# ovencontrol.net
KiCad netlist of a schematic drawn in Altium Designer
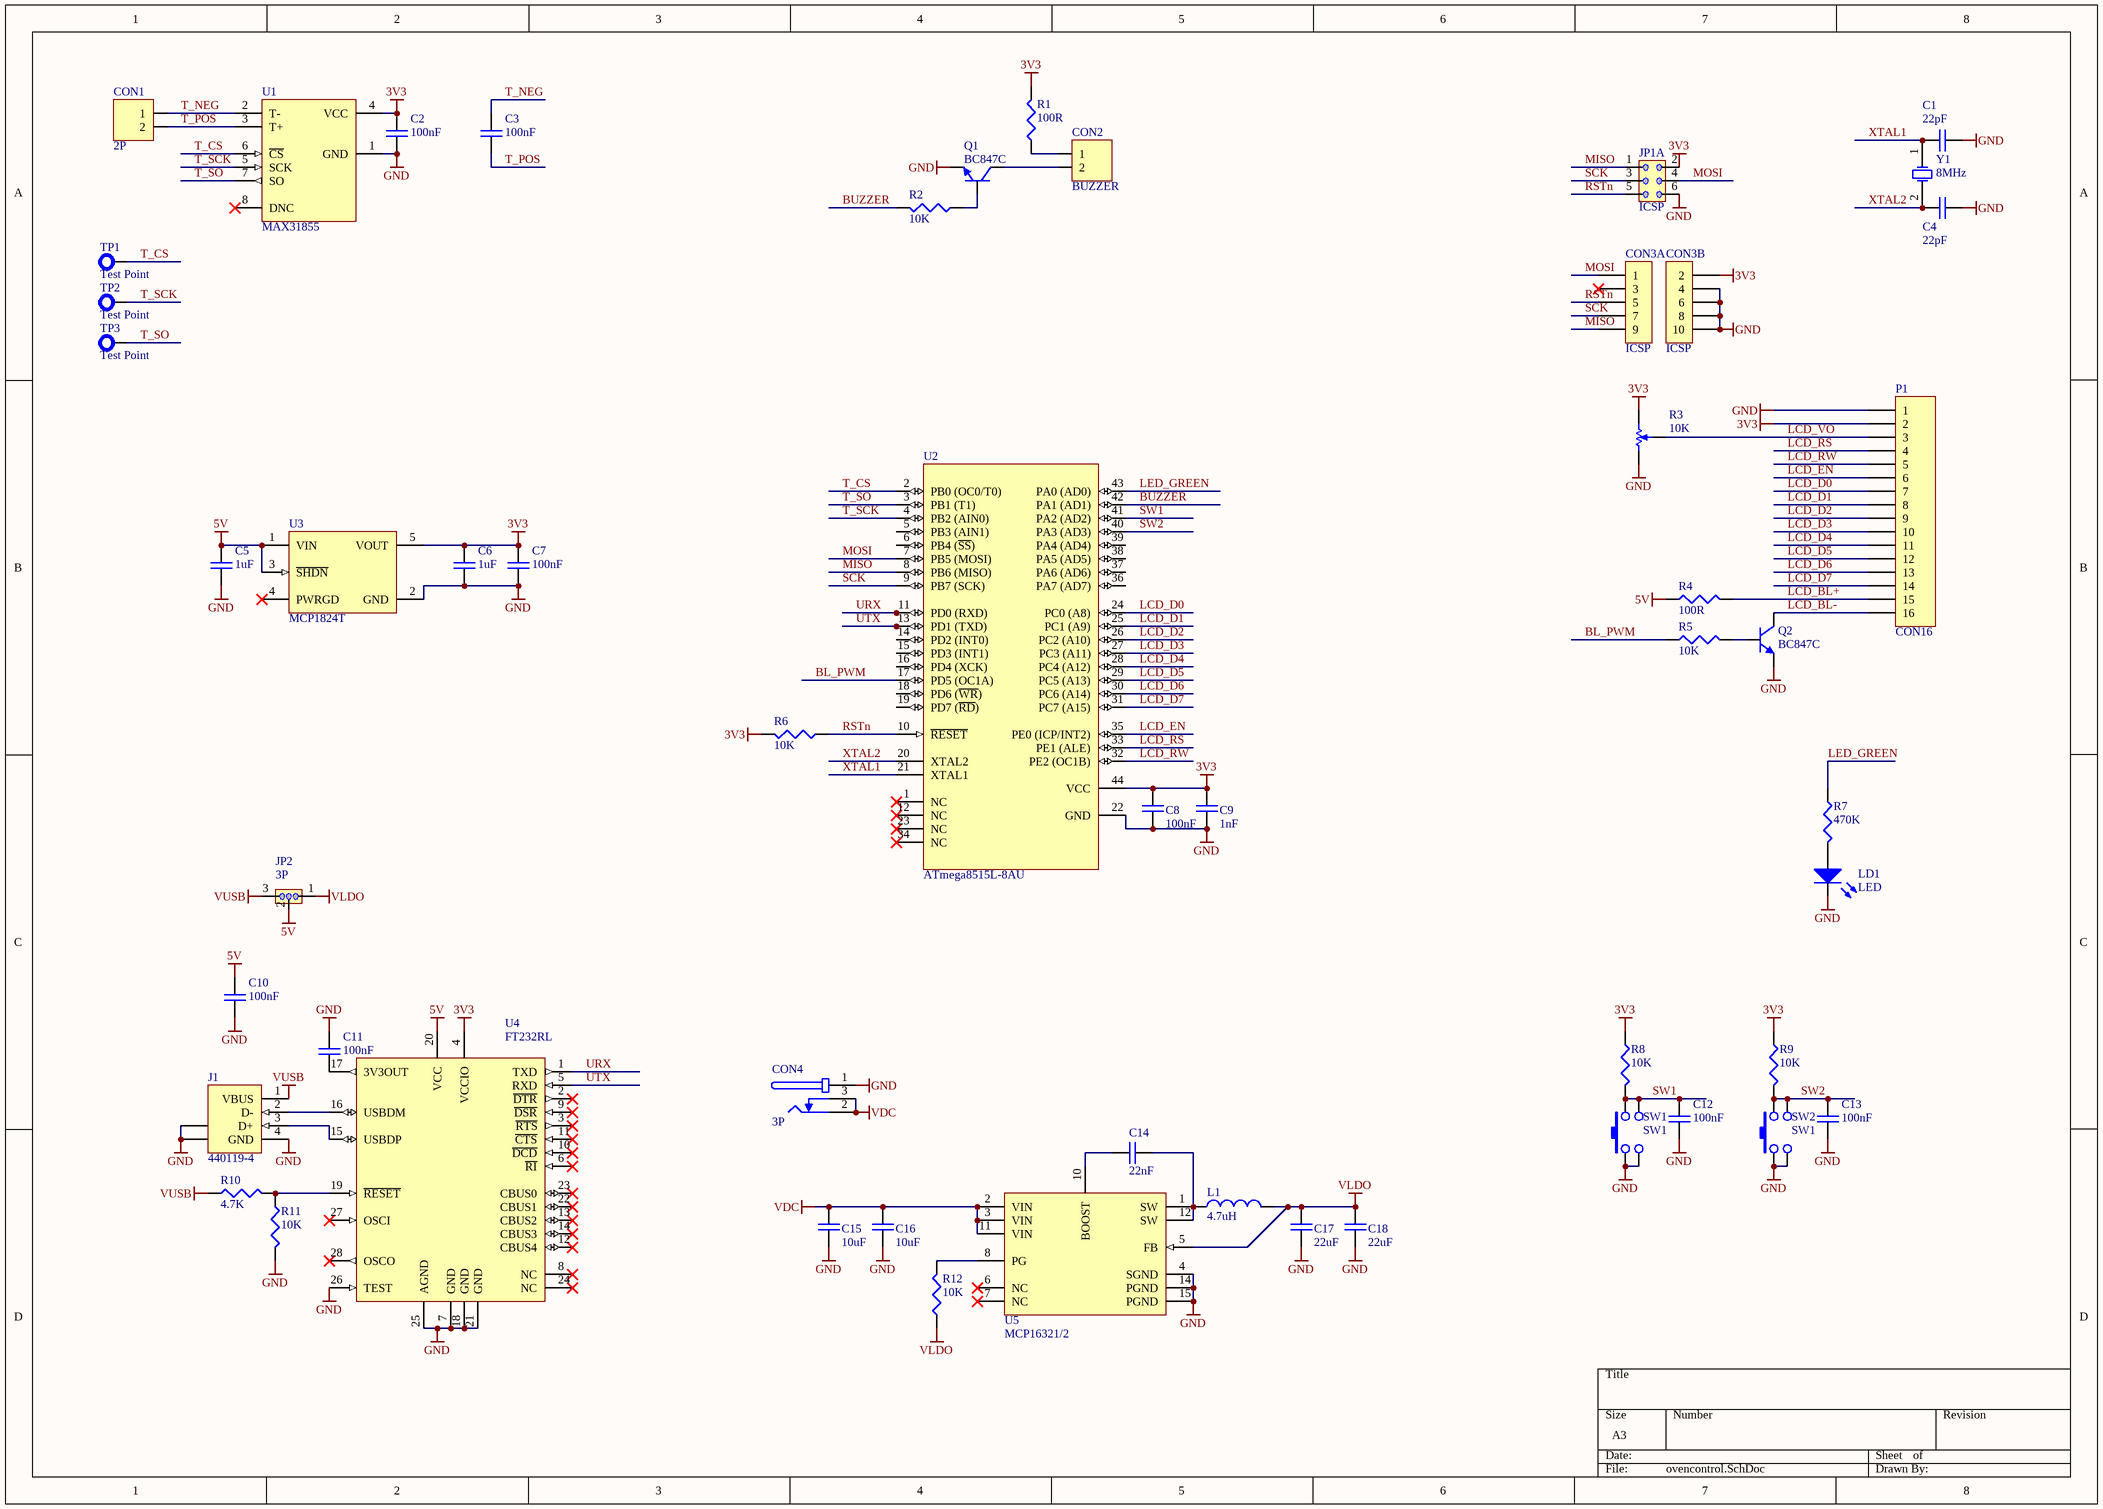
[diagram p0: ovencontrol.SchDoc]

(export (version "E")
  (design (tool "Eeschema 10.0.6"))
  (components
    (comp (ref "C1")
      (value "22pF")
      (footprint "0603")
      (description "Capacitor")
      (fields (field (name "OWNER") "Nuno Brum"))
      (libsource (lib "Alcetronics_Devices") (part "CAP"))
    )
    (comp (ref "C2")
      (value "100nF")
      (footprint "0603")
      (description "Capacitor")
      (fields (field (name "OWNER") "Nuno Brum"))
      (libsource (lib "Alcetronics_Devices") (part "CAP"))
    )
    (comp (ref "C3")
      (value "100nF")
      (footprint "0603")
      (description "Capacitor")
      (fields (field (name "OWNER") "Nuno Brum"))
      (libsource (lib "Alcetronics_Devices") (part "CAP"))
    )
    (comp (ref "C4")
      (value "22pF")
      (footprint "0603")
      (description "Capacitor")
      (fields (field (name "OWNER") "Nuno Brum"))
      (libsource (lib "Alcetronics_Devices") (part "CAP"))
    )
    (comp (ref "C5")
      (value "1uF")
      (footprint "0603")
      (description "Capacitor")
      (fields (field (name "OWNER") "Nuno Brum"))
      (libsource (lib "Alcetronics_Devices") (part "CAP"))
    )
    (comp (ref "C6")
      (value "1uF")
      (footprint "0603")
      (description "Capacitor")
      (fields (field (name "OWNER") "Nuno Brum"))
      (libsource (lib "Alcetronics_Devices") (part "CAP"))
    )
    (comp (ref "C7")
      (value "100nF")
      (footprint "0603")
      (description "Capacitor")
      (fields (field (name "OWNER") "Nuno Brum"))
      (libsource (lib "Alcetronics_Devices") (part "CAP"))
    )
    (comp (ref "C8")
      (value "100nF")
      (footprint "0603")
      (description "Capacitor")
      (fields (field (name "OWNER") "Nuno Brum"))
      (libsource (lib "Alcetronics_Devices") (part "CAP"))
    )
    (comp (ref "C9")
      (value "1nF")
      (footprint "0603")
      (description "Capacitor")
      (fields (field (name "OWNER") "Nuno Brum"))
      (libsource (lib "Alcetronics_Devices") (part "CAP"))
    )
    (comp (ref "C10")
      (value "100nF")
      (footprint "0603")
      (description "Capacitor")
      (fields (field (name "OWNER") "Nuno Brum"))
      (libsource (lib "Alcetronics_Devices") (part "CAP"))
    )
    (comp (ref "C11")
      (value "100nF")
      (footprint "0603")
      (description "Capacitor")
      (fields (field (name "OWNER") "Nuno Brum"))
      (libsource (lib "Alcetronics_Devices") (part "CAP"))
    )
    (comp (ref "C12")
      (value "100nF")
      (footprint "0603")
      (description "Capacitor")
      (fields (field (name "OWNER") "Nuno Brum"))
      (libsource (lib "Alcetronics_Devices") (part "CAP"))
    )
    (comp (ref "C13")
      (value "100nF")
      (footprint "0603")
      (description "Capacitor")
      (fields (field (name "OWNER") "Nuno Brum"))
      (libsource (lib "Alcetronics_Devices") (part "CAP"))
    )
    (comp (ref "C14")
      (value "22nF")
      (footprint "0603")
      (description "Capacitor")
      (fields (field (name "OWNER") "Nuno Brum"))
      (libsource (lib "Alcetronics_Devices") (part "CAP"))
    )
    (comp (ref "C15")
      (value "10uF")
      (footprint "0603")
      (description "Capacitor")
      (fields (field (name "OWNER") "Nuno Brum"))
      (libsource (lib "Alcetronics_Devices") (part "CAP"))
    )
    (comp (ref "C16")
      (value "10uF")
      (footprint "0603")
      (description "Capacitor")
      (fields (field (name "OWNER") "Nuno Brum"))
      (libsource (lib "Alcetronics_Devices") (part "CAP"))
    )
    (comp (ref "C17")
      (value "22uF")
      (footprint "0603")
      (description "Capacitor")
      (fields (field (name "OWNER") "Nuno Brum"))
      (libsource (lib "Alcetronics_Devices") (part "CAP"))
    )
    (comp (ref "C18")
      (value "22uF")
      (footprint "0603")
      (description "Capacitor")
      (fields (field (name "OWNER") "Nuno Brum"))
      (libsource (lib "Alcetronics_Devices") (part "CAP"))
    )
    (comp (ref "CON1")
      (value "2P")
      (footprint "INTERLOCK2-5MM")
      (description "Connector 2 pins")
      (fields (field (name "OWNER") "Rui Rebelo"))
      (libsource (lib "") (part "CON02_1"))
    )
    (comp (ref "CON2")
      (value "BUZZER")
      (footprint "SIP-2")
      (description "Connector 2 pins")
      (fields (field (name "OWNER") "Rui Rebelo"))
      (libsource (lib "Alcetronics_EM") (part "CON02"))
    )
    (comp (ref "CON3")
      (value "ICSP")
      (footprint "IDC-10-F")
      (description "Connector 10 Pins")
      (fields (field (name "OWNER") "António Silva"))
      (libsource (lib "Alcetronics_EM") (part "CON10"))
    )
    (comp (ref "CON4")
      (value "3P")
      (footprint "JACKPOW/PD-2.5MM-TH")
      (description "Jack Power with insertion detect")
      (fields (field (name "OWNER") "Gonçalo Costa"))
      (libsource (lib "Alcetronics_EM") (part "JACK POWER PD"))
    )
    (comp (ref "J1")
      (value "440119-4")
      (footprint "440119")
      (description "USB 1.1, Right Angle, Thru-Hole, B Type, Receptacle, 4 Position, Black")
      (fields (field (name "PUBLISHER") "Altium Limited"))
      (libsource (lib "Alcetronics_EM") (part "440119-4"))
    )
    (comp (ref "JP1")
      (value "ICSP")
      (footprint "DIL-6")
      (description "6-Pin Jumper")
      (fields (field (name "OWNER") "Rui Rebelo"))
      (libsource (lib "Alcetronics_EM") (part "JMP6"))
    )
    (comp (ref "JP2")
      (value "3P")
      (footprint "SIP-3")
      (description "3-Jumper")
      (fields (field (name "OWNER") "Nuno Brum"))
      (libsource (lib "Alcetronics_EM") (part "JMP3"))
    )
    (comp (ref "L1")
      (value "4.7uH")
      (footprint "6X6")
      (description "Inductor")
      (fields (field (name "OWNER") "Nuno Brum"))
      (libsource (lib "Alcetronics_Devices") (part "IND"))
    )
    (comp (ref "LD1")
      (value "LED")
      (footprint "0805@DIODE")
      (description "Light emitting diode")
      (fields (field (name "OWNER") "Nuno Brum"))
      (libsource (lib "Alcetronics_Devices") (part "LED"))
    )
    (comp (ref "P1")
      (value "CON16")
      (footprint "Alcetronics_EM:HDR1X16")
      (description "Header, 16-Pin")
      (fields (field (name "PUBLISHER") "Altium Limited"))
      (libsource (lib "Alcetronics_EM") (part "CON16"))
    )
    (comp (ref "Q1")
      (value "BC847C")
      (footprint "SOT-23@BEC")
      (description "NPN General Purpose Transistor")
      (fields (field (name "OWNER") "Nuno Brum"))
      (libsource (lib "Alcetronics_Devices") (part "NPN"))
    )
    (comp (ref "Q2")
      (value "BC847C")
      (footprint "SOT-23@BEC")
      (description "NPN General Purpose Transistor")
      (fields (field (name "OWNER") "Nuno Brum"))
      (libsource (lib "Alcetronics_Devices") (part "NPN"))
    )
    (comp (ref "R1")
      (value "100R")
      (footprint "0603")
      (description "Resistor")
      (fields (field (name "OWNER") "Nuno Brum"))
      (libsource (lib "Alcetronics_Devices") (part "RES"))
    )
    (comp (ref "R2")
      (value "10K")
      (footprint "0603")
      (description "Resistor")
      (fields (field (name "OWNER") "Nuno Brum"))
      (libsource (lib "Alcetronics_Devices") (part "RES"))
    )
    (comp (ref "R3")
      (value "10K")
      (footprint "Alcetronics_Devices:POT4MM-2")
      (description "Square Trimming Potentiometer")
      (fields (field (name "PUBLISHER") "Altium Limited"))
      (libsource (lib "Alcetronics_Devices") (part "RES Pot"))
    )
    (comp (ref "R4")
      (value "100R")
      (footprint "0603")
      (description "Resistor")
      (fields (field (name "OWNER") "Nuno Brum"))
      (libsource (lib "Alcetronics_Devices") (part "RES"))
    )
    (comp (ref "R5")
      (value "10K")
      (footprint "0603")
      (description "Resistor")
      (fields (field (name "OWNER") "Nuno Brum"))
      (libsource (lib "Alcetronics_Devices") (part "RES"))
    )
    (comp (ref "R6")
      (value "10K")
      (footprint "0603")
      (description "Resistor")
      (fields (field (name "OWNER") "Nuno Brum"))
      (libsource (lib "Alcetronics_Devices") (part "RES"))
    )
    (comp (ref "R7")
      (value "470K")
      (footprint "0603")
      (description "Resistor")
      (fields (field (name "OWNER") "Nuno Brum"))
      (libsource (lib "Alcetronics_Devices") (part "RES"))
    )
    (comp (ref "R8")
      (value "10K")
      (footprint "0603")
      (description "Resistor")
      (fields (field (name "OWNER") "Nuno Brum"))
      (libsource (lib "Alcetronics_Devices") (part "RES"))
    )
    (comp (ref "R9")
      (value "10K")
      (footprint "0603")
      (description "Resistor")
      (fields (field (name "OWNER") "Nuno Brum"))
      (libsource (lib "Alcetronics_Devices") (part "RES"))
    )
    (comp (ref "R10")
      (value "4.7K")
      (footprint "0603")
      (description "Resistor")
      (fields (field (name "OWNER") "Nuno Brum"))
      (libsource (lib "Alcetronics_Devices") (part "RES"))
    )
    (comp (ref "R11")
      (value "10K")
      (footprint "0603")
      (description "Resistor")
      (fields (field (name "OWNER") "Nuno Brum"))
      (libsource (lib "Alcetronics_Devices") (part "RES"))
    )
    (comp (ref "R12")
      (value "10K")
      (footprint "0603")
      (description "Resistor")
      (fields (field (name "OWNER") "Nuno Brum"))
      (libsource (lib "Alcetronics_Devices") (part "RES"))
    )
    (comp (ref "SW1")
      (value "SW1")
      (footprint "MICROSWITCH")
      (description "Switch Push Button")
      (fields (field (name "OWNER") "Nuno Brum"))
      (libsource (lib "Alcetronics_EM") (part "SW1"))
    )
    (comp (ref "SW2")
      (value "SW1")
      (footprint "MICROSWITCH")
      (description "Switch Push Button")
      (fields (field (name "OWNER") "Nuno Brum"))
      (libsource (lib "Alcetronics_EM") (part "SW1"))
    )
    (comp (ref "TP1")
      (value "Test Point")
      (footprint "TERMINAL")
      (description "Test/Probe Point")
      (fields (field (name "OWNER") "Nuno Brum"))
      (libsource (lib "Alcetronics_EM") (part "TEST-PROBE"))
    )
    (comp (ref "TP2")
      (value "Test Point")
      (footprint "TERMINAL")
      (description "Test/Probe Point")
      (fields (field (name "OWNER") "Nuno Brum"))
      (libsource (lib "Alcetronics_EM") (part "TEST-PROBE"))
    )
    (comp (ref "TP3")
      (value "Test Point")
      (footprint "TERMINAL")
      (description "Test/Probe Point")
      (fields (field (name "OWNER") "Nuno Brum"))
      (libsource (lib "Alcetronics_EM") (part "TEST-PROBE"))
    )
    (comp (ref "U1")
      (value "MAX31855")
      (footprint "Alcetronics_IC:SOIC-8")
      (description "Cold-Junction Compensated Thermocouple-to-Digital Converter")
      (libsource (lib "Alcetronics_IC") (part "MAX31855"))
    )
    (comp (ref "U2")
      (value "ATmega8515L-8AU")
      (footprint "Alcetronics_IC:TQFP-44")
      (fields (field (name "PUBLISHER") "Altium Limited"))
      (libsource (lib "Alcetronics_IC") (part "ATmega8515L-8AU"))
    )
    (comp (ref "U3")
      (value "MCP1824T")
      (footprint "SOT-23-5")
      (fields (field (name "PUBLISHER") "Altium Limited"))
      (libsource (lib "Alcetronics_IC") (part "MCP1824T"))
    )
    (comp (ref "U4")
      (value "FT232RL")
      (footprint "Alcetronics_IC:SSOP-28")
      (description "USB UART Asynchronous Serial Data Transfer Chip, SSOP-28, Tube")
      (fields (field (name "PUBLISHER") "Altium Limited"))
      (libsource (lib "Alcetronics_IC") (part "FT232RL"))
    )
    (comp (ref "U5")
      (value "MCP16321/2")
      (footprint "Alcetronics_IC:QFN50P300X300-16V4L")
      (description "24V Input, 1A/2A Output, High Efficiency Synchronous Buck Regulator  with Power Good Indicatio")
      (libsource (lib "Alcetronics_IC") (part "MCP16321/2"))
    )
    (comp (ref "Y1")
      (value "8MHz")
      (footprint "HC-49U")
      (description "Crystal Oscillator")
      (fields (field (name "PUBLISHER") "Altium Limited"))
      (libsource (lib "Alcetronics_Devices") (part "Crystal Oscillator"))
    )
  )
  (nets
    (net (code "1") (name "/BL_PWM") (class "Default")
      (node (ref "R5") (pin "1") (pinfunction "1_1") (pintype "passive"))
      (node (ref "U2") (pin "17") (pinfunction "PD5_(OC1A)_17") (pintype "bidirectional"))
    )
    (net (code "2") (name "/BUZZER") (class "Default")
      (node (ref "R2") (pin "2") (pinfunction "2_2") (pintype "passive"))
      (node (ref "U2") (pin "42") (pinfunction "PA1_(AD1)_42") (pintype "bidirectional"))
    )
    (net (code "3") (name "/LCD_BL+") (class "Default")
      (node (ref "P1") (pin "15") (pinfunction "15_15") (pintype "passive"))
      (node (ref "R4") (pin "2") (pinfunction "2_2") (pintype "passive"))
    )
    (net (code "4") (name "/LCD_BL-") (class "Default")
      (node (ref "P1") (pin "16") (pinfunction "16_16") (pintype "passive"))
      (node (ref "Q2") (pin "C") (pinfunction "C_C") (pintype "passive"))
    )
    (net (code "5") (name "/LCD_D0") (class "Default")
      (node (ref "P1") (pin "7") (pinfunction "7_7") (pintype "passive"))
      (node (ref "U2") (pin "24") (pinfunction "PC0_(A8)_24") (pintype "bidirectional"))
    )
    (net (code "6") (name "/LCD_D1") (class "Default")
      (node (ref "P1") (pin "8") (pinfunction "8_8") (pintype "passive"))
      (node (ref "U2") (pin "25") (pinfunction "PC1_(A9)_25") (pintype "bidirectional"))
    )
    (net (code "7") (name "/LCD_D2") (class "Default")
      (node (ref "P1") (pin "9") (pinfunction "9_9") (pintype "passive"))
      (node (ref "U2") (pin "26") (pinfunction "PC2_(A10)_26") (pintype "bidirectional"))
    )
    (net (code "8") (name "/LCD_D3") (class "Default")
      (node (ref "P1") (pin "10") (pinfunction "10_10") (pintype "passive"))
      (node (ref "U2") (pin "27") (pinfunction "PC3_(A11)_27") (pintype "bidirectional"))
    )
    (net (code "9") (name "/LCD_D4") (class "Default")
      (node (ref "P1") (pin "11") (pinfunction "11_11") (pintype "passive"))
      (node (ref "U2") (pin "28") (pinfunction "PC4_(A12)_28") (pintype "bidirectional"))
    )
    (net (code "10") (name "/LCD_D5") (class "Default")
      (node (ref "P1") (pin "12") (pinfunction "12_12") (pintype "passive"))
      (node (ref "U2") (pin "29") (pinfunction "PC5_(A13)_29") (pintype "bidirectional"))
    )
    (net (code "11") (name "/LCD_D6") (class "Default")
      (node (ref "P1") (pin "13") (pinfunction "13_13") (pintype "passive"))
      (node (ref "U2") (pin "30") (pinfunction "PC6_(A14)_30") (pintype "bidirectional"))
    )
    (net (code "12") (name "/LCD_D7") (class "Default")
      (node (ref "P1") (pin "14") (pinfunction "14_14") (pintype "passive"))
      (node (ref "U2") (pin "31") (pinfunction "PC7_(A15)_31") (pintype "bidirectional"))
    )
    (net (code "13") (name "/LCD_EN") (class "Default")
      (node (ref "P1") (pin "6") (pinfunction "6_6") (pintype "passive"))
      (node (ref "U2") (pin "35") (pinfunction "PE0_(ICP/INT2)_35") (pintype "bidirectional"))
    )
    (net (code "14") (name "/LCD_RS") (class "Default")
      (node (ref "P1") (pin "4") (pinfunction "4_4") (pintype "passive"))
      (node (ref "U2") (pin "33") (pinfunction "PE1_(ALE)_33") (pintype "bidirectional"))
    )
    (net (code "15") (name "/LCD_RW") (class "Default")
      (node (ref "P1") (pin "5") (pinfunction "5_5") (pintype "passive"))
      (node (ref "U2") (pin "32") (pinfunction "PE2_(OC1B)_32") (pintype "bidirectional"))
    )
    (net (code "16") (name "/LCD_VO") (class "Default")
      (node (ref "P1") (pin "3") (pinfunction "3_3") (pintype "passive"))
      (node (ref "R3") (pin "W") (pinfunction "W_W") (pintype "passive"))
    )
    (net (code "17") (name "/LED_GREEN") (class "Default")
      (node (ref "R7") (pin "1") (pinfunction "1_1") (pintype "passive"))
      (node (ref "U2") (pin "43") (pinfunction "PA0_(AD0)_43") (pintype "bidirectional"))
    )
    (net (code "18") (name "/MISO") (class "Default")
      (node (ref "CON3") (pin "9") (pinfunction "9_9") (pintype "passive"))
      (node (ref "JP1") (pin "1") (pinfunction "1_1") (pintype "passive"))
      (node (ref "U2") (pin "8") (pinfunction "PB6_(MISO)_8") (pintype "bidirectional"))
    )
    (net (code "19") (name "/MOSI") (class "Default")
      (node (ref "CON3") (pin "1") (pinfunction "1_1") (pintype "passive"))
      (node (ref "JP1") (pin "4") (pinfunction "4_4") (pintype "passive"))
      (node (ref "U2") (pin "7") (pinfunction "PB5_(MOSI)_7") (pintype "bidirectional"))
    )
    (net (code "20") (name "/RSTn") (class "Default")
      (node (ref "CON3") (pin "5") (pinfunction "5_5") (pintype "passive"))
      (node (ref "JP1") (pin "5") (pinfunction "5_5") (pintype "passive"))
      (node (ref "R6") (pin "2") (pinfunction "2_2") (pintype "passive"))
      (node (ref "U2") (pin "10") (pinfunction "~{RESET}_10") (pintype "input"))
    )
    (net (code "21") (name "/SCK") (class "Default")
      (node (ref "CON3") (pin "7") (pinfunction "7_7") (pintype "passive"))
      (node (ref "JP1") (pin "3") (pinfunction "3_3") (pintype "passive"))
      (node (ref "U2") (pin "9") (pinfunction "PB7_(SCK)_9") (pintype "bidirectional"))
    )
    (net (code "22") (name "/SW1") (class "Default")
      (node (ref "C12") (pin "1") (pinfunction "1_1") (pintype "passive"))
      (node (ref "R8") (pin "2") (pinfunction "2_2") (pintype "passive"))
      (node (ref "SW1") (pin "2") (pinfunction "2_2") (pintype "passive"))
      (node (ref "SW1") (pin "4") (pinfunction "4_4") (pintype "passive"))
      (node (ref "U2") (pin "41") (pinfunction "PA2_(AD2)_41") (pintype "bidirectional"))
    )
    (net (code "23") (name "/SW2") (class "Default")
      (node (ref "C13") (pin "1") (pinfunction "1_1") (pintype "passive"))
      (node (ref "R9") (pin "2") (pinfunction "2_2") (pintype "passive"))
      (node (ref "SW2") (pin "2") (pinfunction "2_2") (pintype "passive"))
      (node (ref "SW2") (pin "4") (pinfunction "4_4") (pintype "passive"))
      (node (ref "U2") (pin "40") (pinfunction "PA3_(AD3)_40") (pintype "bidirectional"))
    )
    (net (code "24") (name "/T_CS") (class "Default")
      (node (ref "TP1") (pin "1") (pinfunction "TP_1") (pintype "passive"))
      (node (ref "U1") (pin "6") (pinfunction "~{CS}_6") (pintype "input"))
      (node (ref "U2") (pin "2") (pinfunction "PB0_(OC0/T0)_2") (pintype "bidirectional"))
    )
    (net (code "25") (name "/T_NEG") (class "Default")
      (node (ref "C3") (pin "1") (pinfunction "1_1") (pintype "passive"))
      (node (ref "CON1") (pin "1") (pinfunction "1_1") (pintype "passive"))
      (node (ref "U1") (pin "2") (pinfunction "T-_2") (pintype "passive"))
    )
    (net (code "26") (name "/T_POS") (class "Default")
      (node (ref "C3") (pin "2") (pinfunction "2_2") (pintype "passive"))
      (node (ref "CON1") (pin "2") (pinfunction "2_2") (pintype "passive"))
      (node (ref "U1") (pin "3") (pinfunction "T+_3") (pintype "passive"))
    )
    (net (code "27") (name "/T_SCK") (class "Default")
      (node (ref "TP2") (pin "1") (pinfunction "TP_1") (pintype "passive"))
      (node (ref "U1") (pin "5") (pinfunction "SCK_5") (pintype "input"))
      (node (ref "U2") (pin "4") (pinfunction "PB2_(AIN0)_4") (pintype "bidirectional"))
    )
    (net (code "28") (name "/T_SO") (class "Default")
      (node (ref "TP3") (pin "1") (pinfunction "TP_1") (pintype "passive"))
      (node (ref "U1") (pin "7") (pinfunction "SO_7") (pintype "output"))
      (node (ref "U2") (pin "3") (pinfunction "PB1_(T1)_3") (pintype "bidirectional"))
    )
    (net (code "29") (name "/URX") (class "Default")
      (node (ref "U2") (pin "11") (pinfunction "PD0_(RXD)_11") (pintype "bidirectional"))
      (node (ref "U4") (pin "1") (pinfunction "TXD_1") (pintype "output"))
    )
    (net (code "30") (name "/UTX") (class "Default")
      (node (ref "U2") (pin "13") (pinfunction "PD1_(TXD)_13") (pintype "bidirectional"))
      (node (ref "U4") (pin "5") (pinfunction "RXD_5") (pintype "input"))
    )
    (net (code "31") (name "/XTAL1") (class "Default")
      (node (ref "C1") (pin "2") (pinfunction "2_2") (pintype "passive"))
      (node (ref "U2") (pin "21") (pinfunction "XTAL1_21") (pintype "passive"))
      (node (ref "Y1") (pin "1") (pinfunction "OSC1_1") (pintype "passive"))
    )
    (net (code "32") (name "/XTAL2") (class "Default")
      (node (ref "C4") (pin "2") (pinfunction "2_2") (pintype "passive"))
      (node (ref "U2") (pin "20") (pinfunction "XTAL2_20") (pintype "passive"))
      (node (ref "Y1") (pin "2") (pinfunction "OSC2_2") (pintype "passive"))
    )
    (net (code "33") (name "3V3") (class "Default")
      (node (ref "C2") (pin "1") (pinfunction "1_1") (pintype "passive"))
      (node (ref "C6") (pin "1") (pinfunction "1_1") (pintype "passive"))
      (node (ref "C7") (pin "1") (pinfunction "1_1") (pintype "passive"))
      (node (ref "C8") (pin "2") (pinfunction "2_2") (pintype "passive"))
      (node (ref "C9") (pin "2") (pinfunction "2_2") (pintype "passive"))
      (node (ref "CON3") (pin "2") (pinfunction "2_2") (pintype "passive"))
      (node (ref "JP1") (pin "2") (pinfunction "2_2") (pintype "passive"))
      (node (ref "P1") (pin "2") (pinfunction "2_2") (pintype "passive"))
      (node (ref "R1") (pin "2") (pinfunction "2_2") (pintype "passive"))
      (node (ref "R3") (pin "CW") (pinfunction "+_CW") (pintype "passive"))
      (node (ref "R6") (pin "1") (pinfunction "1_1") (pintype "passive"))
      (node (ref "R8") (pin "1") (pinfunction "1_1") (pintype "passive"))
      (node (ref "R9") (pin "1") (pinfunction "1_1") (pintype "passive"))
      (node (ref "U1") (pin "4") (pinfunction "VCC_4") (pintype "power_in"))
      (node (ref "U2") (pin "44") (pinfunction "VCC_44") (pintype "power_in"))
      (node (ref "U3") (pin "5") (pinfunction "VOUT_5") (pintype "power_in"))
      (node (ref "U4") (pin "4") (pinfunction "VCCIO_4") (pintype "power_in"))
    )
    (net (code "34") (name "5V") (class "Default")
      (node (ref "C10") (pin "1") (pinfunction "1_1") (pintype "passive"))
      (node (ref "C5") (pin "1") (pinfunction "1_1") (pintype "passive"))
      (node (ref "JP2") (pin "2") (pinfunction "2_2") (pintype "passive"))
      (node (ref "R4") (pin "1") (pinfunction "1_1") (pintype "passive"))
      (node (ref "U3") (pin "1") (pinfunction "VIN_1") (pintype "power_in"))
      (node (ref "U3") (pin "3") (pinfunction "~{SHDN}_3") (pintype "input"))
      (node (ref "U4") (pin "20") (pinfunction "VCC_20") (pintype "power_in"))
    )
    (net (code "35") (name "GND") (class "Default")
      (node (ref "C1") (pin "1") (pinfunction "1_1") (pintype "passive"))
      (node (ref "C10") (pin "2") (pinfunction "2_2") (pintype "passive"))
      (node (ref "C11") (pin "1") (pinfunction "1_1") (pintype "passive"))
      (node (ref "C12") (pin "2") (pinfunction "2_2") (pintype "passive"))
      (node (ref "C13") (pin "2") (pinfunction "2_2") (pintype "passive"))
      (node (ref "C15") (pin "2") (pinfunction "2_2") (pintype "passive"))
      (node (ref "C16") (pin "2") (pinfunction "2_2") (pintype "passive"))
      (node (ref "C17") (pin "2") (pinfunction "2_2") (pintype "passive"))
      (node (ref "C18") (pin "2") (pinfunction "2_2") (pintype "passive"))
      (node (ref "C2") (pin "2") (pinfunction "2_2") (pintype "passive"))
      (node (ref "C4") (pin "1") (pinfunction "1_1") (pintype "passive"))
      (node (ref "C5") (pin "2") (pinfunction "2_2") (pintype "passive"))
      (node (ref "C6") (pin "2") (pinfunction "2_2") (pintype "passive"))
      (node (ref "C7") (pin "2") (pinfunction "2_2") (pintype "passive"))
      (node (ref "C8") (pin "1") (pinfunction "1_1") (pintype "passive"))
      (node (ref "C9") (pin "1") (pinfunction "1_1") (pintype "passive"))
      (node (ref "CON3") (pin "10") (pinfunction "10_10") (pintype "passive"))
      (node (ref "CON3") (pin "4") (pinfunction "4_4") (pintype "passive"))
      (node (ref "CON3") (pin "6") (pinfunction "6_6") (pintype "passive"))
      (node (ref "CON3") (pin "8") (pinfunction "8_8") (pintype "passive"))
      (node (ref "CON4") (pin "1") (pinfunction "1_1") (pintype "passive"))
      (node (ref "J1") (pin "4") (pinfunction "GND_4") (pintype "power_in"))
      (node (ref "J1") (pin "5") (pinfunction "SHLD_5") (pintype "passive"))
      (node (ref "J1") (pin "6") (pinfunction "SHLD_6") (pintype "passive"))
      (node (ref "JP1") (pin "6") (pinfunction "6_6") (pintype "passive"))
      (node (ref "LD1") (pin "K") (pinfunction "K_K") (pintype "passive"))
      (node (ref "P1") (pin "1") (pinfunction "1_1") (pintype "passive"))
      (node (ref "Q1") (pin "E") (pinfunction "E_E") (pintype "passive"))
      (node (ref "Q2") (pin "E") (pinfunction "E_E") (pintype "passive"))
      (node (ref "R11") (pin "2") (pinfunction "2_2") (pintype "passive"))
      (node (ref "R3") (pin "CCW") (pinfunction "-_CCW") (pintype "passive"))
      (node (ref "SW1") (pin "1") (pinfunction "1_1") (pintype "passive"))
      (node (ref "SW1") (pin "3") (pinfunction "3_3") (pintype "passive"))
      (node (ref "SW2") (pin "1") (pinfunction "1_1") (pintype "passive"))
      (node (ref "SW2") (pin "3") (pinfunction "3_3") (pintype "passive"))
      (node (ref "U1") (pin "1") (pinfunction "GND_1") (pintype "power_in"))
      (node (ref "U2") (pin "22") (pinfunction "GND_22") (pintype "power_in"))
      (node (ref "U3") (pin "2") (pinfunction "GND_2") (pintype "power_in"))
      (node (ref "U4") (pin "18") (pinfunction "GND_18") (pintype "power_in"))
      (node (ref "U4") (pin "21") (pinfunction "GND_21") (pintype "power_in"))
      (node (ref "U4") (pin "25") (pinfunction "AGND_25") (pintype "power_in"))
      (node (ref "U4") (pin "26") (pinfunction "TEST_26") (pintype "input"))
      (node (ref "U4") (pin "7") (pinfunction "GND_7") (pintype "power_in"))
      (node (ref "U5") (pin "14") (pinfunction "PGND_14") (pintype "power_in"))
      (node (ref "U5") (pin "15") (pinfunction "PGND_15") (pintype "power_in"))
      (node (ref "U5") (pin "4") (pinfunction "SGND_4") (pintype "power_in"))
    )
    (net (code "36") (name "Net-(C14-Pad2)") (class "Default")
      (node (ref "C14") (pin "2") (pinfunction "2_2") (pintype "passive"))
      (node (ref "L1") (pin "1") (pinfunction "1_1") (pintype "passive"))
      (node (ref "U5") (pin "1") (pinfunction "SW_1") (pintype "power_in"))
      (node (ref "U5") (pin "12") (pinfunction "SW_12") (pintype "power_in"))
    )
    (net (code "37") (name "Net-(CON2-Pad1)") (class "Default")
      (node (ref "CON2") (pin "1") (pinfunction "1_1") (pintype "passive"))
      (node (ref "R1") (pin "1") (pinfunction "1_1") (pintype "passive"))
    )
    (net (code "38") (name "Net-(CON2-Pad2)") (class "Default")
      (node (ref "CON2") (pin "2") (pinfunction "2_2") (pintype "passive"))
      (node (ref "Q1") (pin "C") (pinfunction "C_C") (pintype "passive"))
    )
    (net (code "39") (name "Net-(J1-D+)") (class "Default")
      (node (ref "J1") (pin "3") (pinfunction "D+_3") (pintype "input"))
      (node (ref "U4") (pin "15") (pinfunction "USBDP_15") (pintype "bidirectional"))
    )
    (net (code "40") (name "Net-(J1-D-)") (class "Default")
      (node (ref "J1") (pin "2") (pinfunction "D-_2") (pintype "input"))
      (node (ref "U4") (pin "16") (pinfunction "USBDM_16") (pintype "bidirectional"))
    )
    (net (code "41") (name "Net-(LD1-PadA)") (class "Default")
      (node (ref "LD1") (pin "A") (pinfunction "A_A") (pintype "passive"))
      (node (ref "R7") (pin "2") (pinfunction "2_2") (pintype "passive"))
    )
    (net (code "42") (name "Net-(Q1-PadB)") (class "Default")
      (node (ref "Q1") (pin "B") (pinfunction "B_B") (pintype "passive"))
      (node (ref "R2") (pin "1") (pinfunction "1_1") (pintype "passive"))
    )
    (net (code "43") (name "Net-(Q2-PadB)") (class "Default")
      (node (ref "Q2") (pin "B") (pinfunction "B_B") (pintype "passive"))
      (node (ref "R5") (pin "2") (pinfunction "2_2") (pintype "passive"))
    )
    (net (code "44") (name "Net-(U4-3V3OUT)") (class "Default")
      (node (ref "C11") (pin "2") (pinfunction "2_2") (pintype "passive"))
      (node (ref "U4") (pin "17") (pinfunction "3V3OUT_17") (pintype "output"))
    )
    (net (code "45") (name "Net-(U4-~{RESET})") (class "Default")
      (node (ref "R10") (pin "2") (pinfunction "2_2") (pintype "passive"))
      (node (ref "R11") (pin "1") (pinfunction "1_1") (pintype "passive"))
      (node (ref "U4") (pin "19") (pinfunction "~{RESET}_19") (pintype "input"))
    )
    (net (code "46") (name "Net-(U5-BOOST)") (class "Default")
      (node (ref "C14") (pin "1") (pinfunction "1_1") (pintype "passive"))
      (node (ref "U5") (pin "10") (pinfunction "BOOST_10") (pintype "power_in"))
    )
    (net (code "47") (name "Net-(U5-PG)") (class "Default")
      (node (ref "R12") (pin "1") (pinfunction "1_1") (pintype "passive"))
      (node (ref "U5") (pin "8") (pinfunction "PG_8") (pintype "open_collector"))
    )
    (net (code "48") (name "VDC") (class "Default")
      (node (ref "C15") (pin "1") (pinfunction "1_1") (pintype "passive"))
      (node (ref "C16") (pin "1") (pinfunction "1_1") (pintype "passive"))
      (node (ref "CON4") (pin "2") (pinfunction "2_2") (pintype "passive"))
      (node (ref "CON4") (pin "3") (pinfunction "3_3") (pintype "passive"))
      (node (ref "U5") (pin "11") (pinfunction "VIN_11") (pintype "power_in"))
      (node (ref "U5") (pin "2") (pinfunction "VIN_2") (pintype "power_in"))
      (node (ref "U5") (pin "3") (pinfunction "VIN_3") (pintype "power_in"))
    )
    (net (code "49") (name "VLDO") (class "Default")
      (node (ref "C17") (pin "1") (pinfunction "1_1") (pintype "passive"))
      (node (ref "C18") (pin "1") (pinfunction "1_1") (pintype "passive"))
      (node (ref "JP2") (pin "1") (pinfunction "1_1") (pintype "passive"))
      (node (ref "L1") (pin "2") (pinfunction "2_2") (pintype "passive"))
      (node (ref "R12") (pin "2") (pinfunction "2_2") (pintype "passive"))
      (node (ref "U5") (pin "5") (pinfunction "FB_5") (pintype "input"))
    )
    (net (code "50") (name "VUSB") (class "Default")
      (node (ref "J1") (pin "1") (pinfunction "VBUS_1") (pintype "power_in"))
      (node (ref "JP2") (pin "3") (pinfunction "3_3") (pintype "passive"))
      (node (ref "R10") (pin "1") (pinfunction "1_1") (pintype "passive"))
    )
    (net (code "51") (name "unconnected-(CON3-Pad3)") (class "Default")
      (node (ref "CON3") (pin "3") (pinfunction "3_3") (pintype "passive+no_connect"))
    )
    (net (code "52") (name "unconnected-(U1-DNC-Pad8)") (class "Default")
      (node (ref "U1") (pin "8") (pinfunction "DNC_8") (pintype "tri_state+no_connect"))
    )
    (net (code "53") (name "unconnected-(U2-NC-Pad1)") (class "Default")
      (node (ref "U2") (pin "1") (pinfunction "NC_1") (pintype "passive+no_connect"))
    )
    (net (code "54") (name "unconnected-(U2-NC-Pad12)") (class "Default")
      (node (ref "U2") (pin "12") (pinfunction "NC_12") (pintype "passive+no_connect"))
    )
    (net (code "55") (name "unconnected-(U2-NC-Pad23)") (class "Default")
      (node (ref "U2") (pin "23") (pinfunction "NC_23") (pintype "passive+no_connect"))
    )
    (net (code "56") (name "unconnected-(U2-NC-Pad34)") (class "Default")
      (node (ref "U2") (pin "34") (pinfunction "NC_34") (pintype "passive+no_connect"))
    )
    (net (code "57") (name "unconnected-(U2-PA4_(AD4)-Pad39)") (class "Default")
      (node (ref "U2") (pin "39") (pinfunction "PA4_(AD4)_39") (pintype "bidirectional"))
    )
    (net (code "58") (name "unconnected-(U2-PA5_(AD5)-Pad38)") (class "Default")
      (node (ref "U2") (pin "38") (pinfunction "PA5_(AD5)_38") (pintype "bidirectional"))
    )
    (net (code "59") (name "unconnected-(U2-PA6_(AD6)-Pad37)") (class "Default")
      (node (ref "U2") (pin "37") (pinfunction "PA6_(AD6)_37") (pintype "bidirectional"))
    )
    (net (code "60") (name "unconnected-(U2-PA7_(AD7)-Pad36)") (class "Default")
      (node (ref "U2") (pin "36") (pinfunction "PA7_(AD7)_36") (pintype "bidirectional"))
    )
    (net (code "61") (name "unconnected-(U2-PB3_(AIN1)-Pad5)") (class "Default")
      (node (ref "U2") (pin "5") (pinfunction "PB3_(AIN1)_5") (pintype "bidirectional"))
    )
    (net (code "62") (name "unconnected-(U2-PB4_(~{SS})-Pad6)") (class "Default")
      (node (ref "U2") (pin "6") (pinfunction "PB4_(~{SS})_6") (pintype "bidirectional"))
    )
    (net (code "63") (name "unconnected-(U2-PD2_(INT0)-Pad14)") (class "Default")
      (node (ref "U2") (pin "14") (pinfunction "PD2_(INT0)_14") (pintype "bidirectional"))
    )
    (net (code "64") (name "unconnected-(U2-PD3_(INT1)-Pad15)") (class "Default")
      (node (ref "U2") (pin "15") (pinfunction "PD3_(INT1)_15") (pintype "bidirectional"))
    )
    (net (code "65") (name "unconnected-(U2-PD4_(XCK)-Pad16)") (class "Default")
      (node (ref "U2") (pin "16") (pinfunction "PD4_(XCK)_16") (pintype "bidirectional"))
    )
    (net (code "66") (name "unconnected-(U2-PD6_(~{WR})-Pad18)") (class "Default")
      (node (ref "U2") (pin "18") (pinfunction "PD6_(~{WR})_18") (pintype "bidirectional"))
    )
    (net (code "67") (name "unconnected-(U2-PD7_(~{RD})-Pad19)") (class "Default")
      (node (ref "U2") (pin "19") (pinfunction "PD7_(~{RD})_19") (pintype "bidirectional"))
    )
    (net (code "68") (name "unconnected-(U3-PWRGD-Pad4)") (class "Default")
      (node (ref "U3") (pin "4") (pinfunction "PWRGD_4") (pintype "power_in+no_connect"))
    )
    (net (code "69") (name "unconnected-(U4-CBUS0-Pad23)") (class "Default")
      (node (ref "U4") (pin "23") (pinfunction "CBUS0_23") (pintype "bidirectional+no_connect"))
    )
    (net (code "70") (name "unconnected-(U4-CBUS1-Pad22)") (class "Default")
      (node (ref "U4") (pin "22") (pinfunction "CBUS1_22") (pintype "bidirectional+no_connect"))
    )
    (net (code "71") (name "unconnected-(U4-CBUS2-Pad13)") (class "Default")
      (node (ref "U4") (pin "13") (pinfunction "CBUS2_13") (pintype "bidirectional+no_connect"))
    )
    (net (code "72") (name "unconnected-(U4-CBUS3-Pad14)") (class "Default")
      (node (ref "U4") (pin "14") (pinfunction "CBUS3_14") (pintype "bidirectional+no_connect"))
    )
    (net (code "73") (name "unconnected-(U4-CBUS4-Pad12)") (class "Default")
      (node (ref "U4") (pin "12") (pinfunction "CBUS4_12") (pintype "bidirectional+no_connect"))
    )
    (net (code "74") (name "unconnected-(U4-NC-Pad8)") (class "Default")
      (node (ref "U4") (pin "8") (pinfunction "NC_8") (pintype "passive+no_connect"))
    )
    (net (code "75") (name "unconnected-(U4-NC-Pad24)") (class "Default")
      (node (ref "U4") (pin "24") (pinfunction "NC_24") (pintype "passive+no_connect"))
    )
    (net (code "76") (name "unconnected-(U4-OSCI-Pad27)") (class "Default")
      (node (ref "U4") (pin "27") (pinfunction "OSCI_27") (pintype "input+no_connect"))
    )
    (net (code "77") (name "unconnected-(U4-OSCO-Pad28)") (class "Default")
      (node (ref "U4") (pin "28") (pinfunction "OSCO_28") (pintype "output+no_connect"))
    )
    (net (code "78") (name "unconnected-(U4-~{CTS}-Pad11)") (class "Default")
      (node (ref "U4") (pin "11") (pinfunction "~{CTS}_11") (pintype "input+no_connect"))
    )
    (net (code "79") (name "unconnected-(U4-~{DCD}-Pad10)") (class "Default")
      (node (ref "U4") (pin "10") (pinfunction "~{DCD}_10") (pintype "input+no_connect"))
    )
    (net (code "80") (name "unconnected-(U4-~{DSR}-Pad9)") (class "Default")
      (node (ref "U4") (pin "9") (pinfunction "~{DSR}_9") (pintype "input+no_connect"))
    )
    (net (code "81") (name "unconnected-(U4-~{DTR}-Pad2)") (class "Default")
      (node (ref "U4") (pin "2") (pinfunction "~{DTR}_2") (pintype "output+no_connect"))
    )
    (net (code "82") (name "unconnected-(U4-~{RI}-Pad6)") (class "Default")
      (node (ref "U4") (pin "6") (pinfunction "~{RI}_6") (pintype "input+no_connect"))
    )
    (net (code "83") (name "unconnected-(U4-~{RTS}-Pad3)") (class "Default")
      (node (ref "U4") (pin "3") (pinfunction "~{RTS}_3") (pintype "output+no_connect"))
    )
    (net (code "84") (name "unconnected-(U5-NC-Pad6)") (class "Default")
      (node (ref "U5") (pin "6") (pinfunction "NC_6") (pintype "passive+no_connect"))
    )
    (net (code "85") (name "unconnected-(U5-NC-Pad7)") (class "Default")
      (node (ref "U5") (pin "7") (pinfunction "NC_7") (pintype "passive+no_connect"))
    )
  )
)
